# ncp-1117.net
KiCad netlist of a schematic drawn in EAGLE
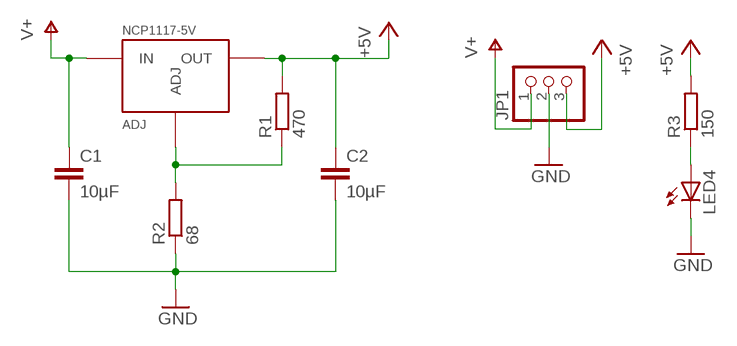
[diagram p0: schematic, sheet 1]

(export (version "E")
  (design (tool "Eeschema 10.0.6"))
  (components
    (comp (ref "C1")
      (value "10µF")
      (footprint "eagle-import:C0805")
      (libsource (lib "eagle-import") (part "C-EUC0805"))
    )
    (comp (ref "C2")
      (value "10µF")
      (footprint "eagle-import:C0805")
      (libsource (lib "eagle-import") (part "C-EUC0805"))
    )
    (comp (ref "JP1")
      (value "PINHD-1X3")
      (footprint "eagle-import:1X03")
      (libsource (lib "eagle-import") (part "PINHD-1X3"))
    )
    (comp (ref "LED4")
      (value "LEDCHIP-LED0603")
      (footprint "eagle-import:CHIP-LED0603")
      (libsource (lib "eagle-import") (part "LEDCHIP-LED0603"))
    )
    (comp (ref "NCP1117-5V")
      (value "ADJ")
      (footprint "eagle-import:TO252")
      (libsource (lib "eagle-import") (part "REGULATOR-TLV1117TO-252"))
    )
    (comp (ref "R1")
      (value "470")
      (footprint "eagle-import:R0603")
      (libsource (lib "eagle-import") (part "R-EU_R0603"))
    )
    (comp (ref "R2")
      (value "68")
      (footprint "eagle-import:R0603")
      (libsource (lib "eagle-import") (part "R-EU_R0603"))
    )
    (comp (ref "R3")
      (value "150")
      (footprint "eagle-import:R0603")
      (libsource (lib "eagle-import") (part "R-EU_R0603"))
    )
  )
  (nets
    (net (code "1") (name "+5V") (class "Default")
      (node (ref "C2") (pin "1") (pinfunction "1_1") (pintype "passive"))
      (node (ref "JP1") (pin "3") (pinfunction "3_3") (pintype "passive"))
      (node (ref "NCP1117-5V") (pin "3") (pinfunction "OUT_3") (pintype "bidirectional"))
      (node (ref "R1") (pin "2") (pinfunction "2_2") (pintype "passive"))
      (node (ref "R3") (pin "2") (pinfunction "2_2") (pintype "passive"))
    )
    (net (code "2") (name "GND") (class "Default")
      (node (ref "C1") (pin "2") (pinfunction "2_2") (pintype "passive"))
      (node (ref "C2") (pin "2") (pinfunction "2_2") (pintype "passive"))
      (node (ref "JP1") (pin "2") (pinfunction "2_2") (pintype "passive"))
      (node (ref "LED4") (pin "C") (pinfunction "C_C") (pintype "passive"))
      (node (ref "R2") (pin "1") (pinfunction "1_1") (pintype "passive"))
    )
    (net (code "3") (name "Net-(LED4-PadA)") (class "Default")
      (node (ref "LED4") (pin "A") (pinfunction "A_A") (pintype "passive"))
      (node (ref "R3") (pin "1") (pinfunction "1_1") (pintype "passive"))
    )
    (net (code "4") (name "Net-(NCP1117-5V-ADJ)") (class "Default")
      (node (ref "NCP1117-5V") (pin "1") (pinfunction "ADJ_1") (pintype "bidirectional"))
      (node (ref "R1") (pin "1") (pinfunction "1_1") (pintype "passive"))
      (node (ref "R2") (pin "2") (pinfunction "2_2") (pintype "passive"))
    )
    (net (code "5") (name "V+") (class "Default")
      (node (ref "C1") (pin "1") (pinfunction "1_1") (pintype "passive"))
      (node (ref "JP1") (pin "1") (pinfunction "1_1") (pintype "passive"))
      (node (ref "NCP1117-5V") (pin "2") (pinfunction "IN_2") (pintype "bidirectional"))
    )
  )
)
